# Soldeerbout_P5.net
KiCad netlist of a schematic drawn in Altium Designer
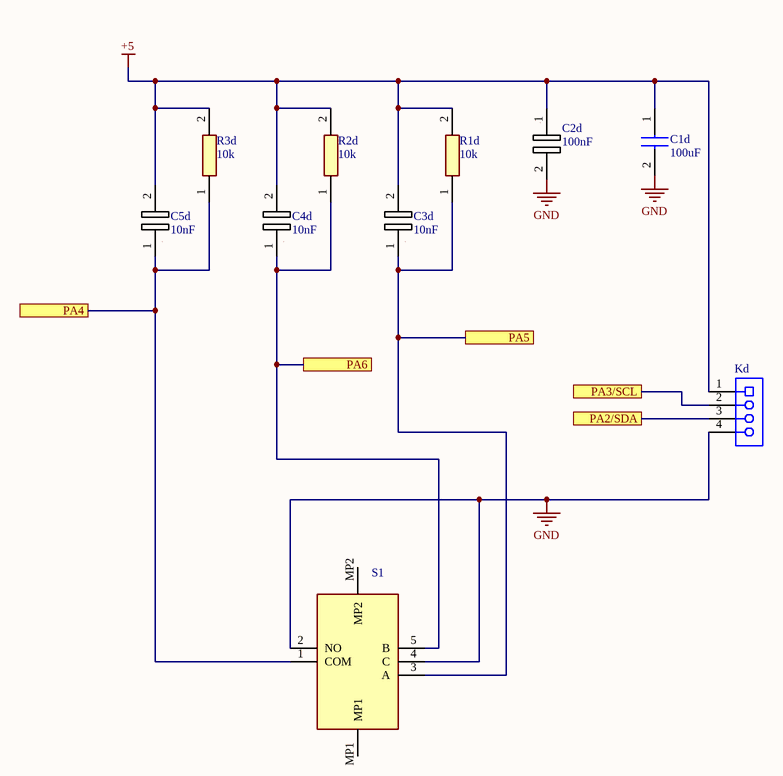
[diagram p0: Soldeerbout_P5.SchDoc]

(export (version "E")
  (design (tool "Eeschema 10.0.6"))
  (components
    (comp (ref "C1d")
      (value "100uF")
      (footprint "SamacSys:CAPPRD350W52D800H1300")
      (description "Capacitor")
      (fields (field (name "MANUFACTURER_PART_NUMBER") "860020674015"))
      (libsource (lib "SamacSys") (part "860020674015"))
    )
    (comp (ref "C2d")
      (value "100nF")
      (footprint "SamacSys:0805")
      (description "Resistor")
      (fields (field (name "MANUFACTURER_PART_NUMBER") "ESR10EZPJ183"))
      (libsource (lib "SamacSys") (part "ESR10EZPJ183_1"))
    )
    (comp (ref "C3d")
      (value "10nF")
      (footprint "SamacSys:0805")
      (description "Resistor")
      (fields (field (name "MANUFACTURER_PART_NUMBER") "ESR10EZPJ183"))
      (libsource (lib "SamacSys") (part "ESR10EZPJ183_1"))
    )
    (comp (ref "C4d")
      (value "10nF")
      (footprint "SamacSys:0805")
      (description "Resistor")
      (fields (field (name "MANUFACTURER_PART_NUMBER") "ESR10EZPJ183"))
      (libsource (lib "SamacSys") (part "ESR10EZPJ183_1"))
    )
    (comp (ref "C5d")
      (value "10nF")
      (footprint "SamacSys:0805")
      (description "Resistor")
      (fields (field (name "MANUFACTURER_PART_NUMBER") "ESR10EZPJ183"))
      (libsource (lib "SamacSys") (part "ESR10EZPJ183_1"))
    )
    (comp (ref "Kd")
      (value "61300411821")
      (footprint "61300411821")
      (description "WR-PHD Socket Header, THT, pitch 2.54mm, Single Row, Vertical, 4p")
      (fields (field (name "MANUFACTURER") "Wurth Elektronik"))
      (libsource (lib "SamacSys") (part "61300411821"))
    )
    (comp (ref "R1d")
      (value "10k")
      (footprint "SamacSys:0805")
      (description "Resistor")
      (fields (field (name "MANUFACTURER_PART_NUMBER") "ESR10EZPJ183"))
      (libsource (lib "SamacSys") (part "ESR10EZPJ183"))
    )
    (comp (ref "R2d")
      (value "10k")
      (footprint "SamacSys:0805")
      (description "Resistor")
      (fields (field (name "MANUFACTURER_PART_NUMBER") "ESR10EZPJ183"))
      (libsource (lib "SamacSys") (part "ESR10EZPJ183"))
    )
    (comp (ref "R3d")
      (value "10k")
      (footprint "SamacSys:0805")
      (description "Resistor")
      (fields (field (name "MANUFACTURER_PART_NUMBER") "ESR10EZPJ183"))
      (libsource (lib "SamacSys") (part "ESR10EZPJ183"))
    )
    (comp (ref "S1")
      (value "482016514001")
      (footprint "SamacSys:482016514001")
      (description "Switch")
      (fields (field (name "MOUSER2 PART NUMBER") "710-482016514001"))
      (libsource (lib "*") (part "482016514001"))
    )
  )
  (nets
    (net (code "1") (name "+5") (class "Default")
      (node (ref "C1d") (pin "1") (pinfunction "+_1") (pintype "passive"))
      (node (ref "C2d") (pin "1") (pinfunction "1_1") (pintype "passive"))
      (node (ref "C3d") (pin "2") (pinfunction "2_2") (pintype "passive"))
      (node (ref "C4d") (pin "2") (pinfunction "2_2") (pintype "passive"))
      (node (ref "C5d") (pin "2") (pinfunction "2_2") (pintype "passive"))
      (node (ref "Kd") (pin "1") (pinfunction "1_1") (pintype "passive"))
      (node (ref "R1d") (pin "2") (pinfunction "2_2") (pintype "passive"))
      (node (ref "R2d") (pin "2") (pinfunction "2_2") (pintype "passive"))
      (node (ref "R3d") (pin "2") (pinfunction "2_2") (pintype "passive"))
    )
    (net (code "2") (name "/PA2{slash}SDA") (class "Default")
      (node (ref "Kd") (pin "3") (pinfunction "3_3") (pintype "passive"))
    )
    (net (code "3") (name "/PA3{slash}SCL") (class "Default")
      (node (ref "Kd") (pin "2") (pinfunction "2_2") (pintype "passive"))
    )
    (net (code "4") (name "/PA4") (class "Default")
      (node (ref "C5d") (pin "1") (pinfunction "1_1") (pintype "passive"))
      (node (ref "R3d") (pin "1") (pinfunction "1_1") (pintype "passive"))
      (node (ref "S1") (pin "1") (pinfunction "COM_1") (pintype "passive"))
    )
    (net (code "5") (name "/PA5") (class "Default")
      (node (ref "C3d") (pin "1") (pinfunction "1_1") (pintype "passive"))
      (node (ref "R1d") (pin "1") (pinfunction "1_1") (pintype "passive"))
      (node (ref "S1") (pin "3") (pinfunction "A_3") (pintype "passive"))
    )
    (net (code "6") (name "/PA6") (class "Default")
      (node (ref "C4d") (pin "1") (pinfunction "1_1") (pintype "passive"))
      (node (ref "R2d") (pin "1") (pinfunction "1_1") (pintype "passive"))
      (node (ref "S1") (pin "5") (pinfunction "B_5") (pintype "passive"))
    )
    (net (code "7") (name "GND") (class "Default")
      (node (ref "C1d") (pin "2") (pinfunction "-_2") (pintype "passive"))
      (node (ref "C2d") (pin "2") (pinfunction "2_2") (pintype "passive"))
      (node (ref "Kd") (pin "4") (pinfunction "4_4") (pintype "passive"))
      (node (ref "S1") (pin "2") (pinfunction "NO_2") (pintype "passive"))
      (node (ref "S1") (pin "4") (pinfunction "C_4") (pintype "passive"))
    )
    (net (code "8") (name "unconnected-(S1-PadMP1)") (class "Default")
      (node (ref "S1") (pin "MP1") (pinfunction "MP1_MP1") (pintype "passive"))
    )
    (net (code "9") (name "unconnected-(S1-PadMP2)") (class "Default")
      (node (ref "S1") (pin "MP2") (pinfunction "MP2_MP2") (pintype "passive"))
    )
  )
)
